# 1LED_pulldown.net
KiCad netlist of a schematic drawn in EAGLE
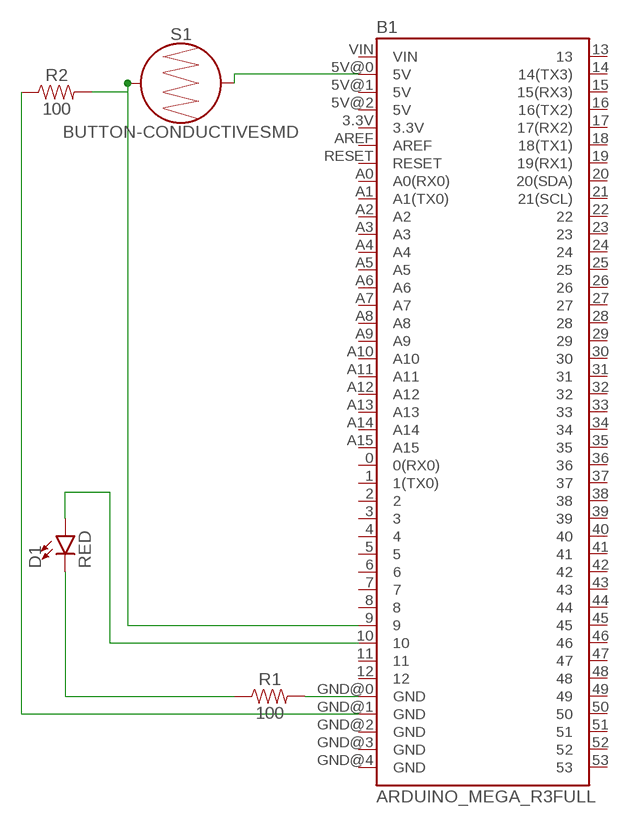
[diagram p0: schematic, sheet 1]

(export (version "E")
  (design (tool "Eeschema 10.0.6"))
  (components
    (comp (ref "B1")
      (value "ARDUINO_MEGA_R3FULL")
      (footprint "eagle-import:ARDUINO_MEGA")
      (libsource (lib "eagle-import") (part "ARDUINO_MEGA_R3FULL"))
    )
    (comp (ref "D1")
      (value "RED")
      (footprint "eagle-import:LED-0603")
      (libsource (lib "eagle-import") (part "LED-RED0603"))
    )
    (comp (ref "R1")
      (value "100")
      (footprint "eagle-import:0603")
      (libsource (lib "eagle-import") (part "100OHM-0603-1/4W-5%"))
    )
    (comp (ref "R2")
      (value "100")
      (footprint "eagle-import:0603")
      (libsource (lib "eagle-import") (part "100OHM-0603-1/4W-5%"))
    )
    (comp (ref "S1")
      (value "BUTTON-CONDUCTIVESMD")
      (footprint "eagle-import:BUTTON-CONDUCTIVE")
      (libsource (lib "eagle-import") (part "BUTTON-CONDUCTIVESMD"))
    )
  )
  (nets
    (net (code "1") (name "Net-(B1-5V-Pad5V@0)") (class "Default")
      (node (ref "B1") (pin "5V@0") (pinfunction "5V_5V@0") (pintype "bidirectional"))
      (node (ref "S1") (pin "2") (pinfunction "2_2") (pintype "passive"))
    )
    (net (code "2") (name "Net-(B1-GND-PadGND@0)") (class "Default")
      (node (ref "B1") (pin "GND@0") (pinfunction "GND_GND@0") (pintype "bidirectional"))
      (node (ref "R1") (pin "2") (pinfunction "2_2") (pintype "passive"))
    )
    (net (code "3") (name "Net-(B1-GND-PadGND@1)") (class "Default")
      (node (ref "B1") (pin "GND@1") (pinfunction "GND_GND@1") (pintype "bidirectional"))
      (node (ref "R2") (pin "1") (pinfunction "1_1") (pintype "passive"))
    )
    (net (code "4") (name "Net-(B1-Pad9)") (class "Default")
      (node (ref "B1") (pin "9") (pinfunction "9_9") (pintype "bidirectional"))
      (node (ref "R2") (pin "2") (pinfunction "2_2") (pintype "passive"))
      (node (ref "S1") (pin "1") (pinfunction "1_1") (pintype "passive"))
    )
    (net (code "5") (name "Net-(B1-Pad10)") (class "Default")
      (node (ref "B1") (pin "10") (pinfunction "10_10") (pintype "bidirectional"))
      (node (ref "D1") (pin "A") (pinfunction "A_A") (pintype "passive"))
    )
    (net (code "6") (name "Net-(D1-PadC)") (class "Default")
      (node (ref "D1") (pin "C") (pinfunction "C_C") (pintype "passive"))
      (node (ref "R1") (pin "1") (pinfunction "1_1") (pintype "passive"))
    )
    (net (code "7") (name "unconnected-(B1-0(RX0)-Pad0)") (class "Default")
      (node (ref "B1") (pin "0") (pinfunction "0(RX0)_0") (pintype "bidirectional"))
    )
    (net (code "8") (name "unconnected-(B1-1(TX0)-Pad1)") (class "Default")
      (node (ref "B1") (pin "1") (pinfunction "1(TX0)_1") (pintype "bidirectional"))
    )
    (net (code "9") (name "unconnected-(B1-5V-Pad5V@1)") (class "Default")
      (node (ref "B1") (pin "5V@1") (pinfunction "5V_5V@1") (pintype "bidirectional"))
    )
    (net (code "10") (name "unconnected-(B1-5V-Pad5V@2)") (class "Default")
      (node (ref "B1") (pin "5V@2") (pinfunction "5V_5V@2") (pintype "bidirectional"))
    )
    (net (code "11") (name "unconnected-(B1-14(TX3)-Pad14)") (class "Default")
      (node (ref "B1") (pin "14") (pinfunction "14(TX3)_14") (pintype "bidirectional"))
    )
    (net (code "12") (name "unconnected-(B1-15(RX3)-Pad15)") (class "Default")
      (node (ref "B1") (pin "15") (pinfunction "15(RX3)_15") (pintype "bidirectional"))
    )
    (net (code "13") (name "unconnected-(B1-16(TX2)-Pad16)") (class "Default")
      (node (ref "B1") (pin "16") (pinfunction "16(TX2)_16") (pintype "bidirectional"))
    )
    (net (code "14") (name "unconnected-(B1-17(RX2)-Pad17)") (class "Default")
      (node (ref "B1") (pin "17") (pinfunction "17(RX2)_17") (pintype "bidirectional"))
    )
    (net (code "15") (name "unconnected-(B1-18(TX1)-Pad18)") (class "Default")
      (node (ref "B1") (pin "18") (pinfunction "18(TX1)_18") (pintype "bidirectional"))
    )
    (net (code "16") (name "unconnected-(B1-19(RX1)-Pad19)") (class "Default")
      (node (ref "B1") (pin "19") (pinfunction "19(RX1)_19") (pintype "bidirectional"))
    )
    (net (code "17") (name "unconnected-(B1-20(SDA)-Pad20)") (class "Default")
      (node (ref "B1") (pin "20") (pinfunction "20(SDA)_20") (pintype "bidirectional"))
    )
    (net (code "18") (name "unconnected-(B1-21(SCL)-Pad21)") (class "Default")
      (node (ref "B1") (pin "21") (pinfunction "21(SCL)_21") (pintype "bidirectional"))
    )
    (net (code "19") (name "unconnected-(B1-A0(RX0)-PadA0)") (class "Default")
      (node (ref "B1") (pin "A0") (pinfunction "A0(RX0)_A0") (pintype "bidirectional"))
    )
    (net (code "20") (name "unconnected-(B1-A1(TX0)-PadA1)") (class "Default")
      (node (ref "B1") (pin "A1") (pinfunction "A1(TX0)_A1") (pintype "bidirectional"))
    )
    (net (code "21") (name "unconnected-(B1-GND-PadGND@2)") (class "Default")
      (node (ref "B1") (pin "GND@2") (pinfunction "GND_GND@2") (pintype "bidirectional"))
    )
    (net (code "22") (name "unconnected-(B1-GND-PadGND@3)") (class "Default")
      (node (ref "B1") (pin "GND@3") (pinfunction "GND_GND@3") (pintype "bidirectional"))
    )
    (net (code "23") (name "unconnected-(B1-GND-PadGND@4)") (class "Default")
      (node (ref "B1") (pin "GND@4") (pinfunction "GND_GND@4") (pintype "bidirectional"))
    )
    (net (code "24") (name "unconnected-(B1-Pad2)") (class "Default")
      (node (ref "B1") (pin "2") (pinfunction "2_2") (pintype "bidirectional"))
    )
    (net (code "25") (name "unconnected-(B1-Pad3)") (class "Default")
      (node (ref "B1") (pin "3") (pinfunction "3_3") (pintype "bidirectional"))
    )
    (net (code "26") (name "unconnected-(B1-Pad3.3V)") (class "Default")
      (node (ref "B1") (pin "3.3V") (pinfunction "3.3V_3.3V") (pintype "bidirectional"))
    )
    (net (code "27") (name "unconnected-(B1-Pad4)") (class "Default")
      (node (ref "B1") (pin "4") (pinfunction "4_4") (pintype "bidirectional"))
    )
    (net (code "28") (name "unconnected-(B1-Pad5)") (class "Default")
      (node (ref "B1") (pin "5") (pinfunction "5_5") (pintype "bidirectional"))
    )
    (net (code "29") (name "unconnected-(B1-Pad6)") (class "Default")
      (node (ref "B1") (pin "6") (pinfunction "6_6") (pintype "bidirectional"))
    )
    (net (code "30") (name "unconnected-(B1-Pad7)") (class "Default")
      (node (ref "B1") (pin "7") (pinfunction "7_7") (pintype "bidirectional"))
    )
    (net (code "31") (name "unconnected-(B1-Pad8)") (class "Default")
      (node (ref "B1") (pin "8") (pinfunction "8_8") (pintype "bidirectional"))
    )
    (net (code "32") (name "unconnected-(B1-Pad11)") (class "Default")
      (node (ref "B1") (pin "11") (pinfunction "11_11") (pintype "bidirectional"))
    )
    (net (code "33") (name "unconnected-(B1-Pad12)") (class "Default")
      (node (ref "B1") (pin "12") (pinfunction "12_12") (pintype "bidirectional"))
    )
    (net (code "34") (name "unconnected-(B1-Pad13)") (class "Default")
      (node (ref "B1") (pin "13") (pinfunction "13_13") (pintype "bidirectional"))
    )
    (net (code "35") (name "unconnected-(B1-Pad22)") (class "Default")
      (node (ref "B1") (pin "22") (pinfunction "22_22") (pintype "bidirectional"))
    )
    (net (code "36") (name "unconnected-(B1-Pad23)") (class "Default")
      (node (ref "B1") (pin "23") (pinfunction "23_23") (pintype "bidirectional"))
    )
    (net (code "37") (name "unconnected-(B1-Pad24)") (class "Default")
      (node (ref "B1") (pin "24") (pinfunction "24_24") (pintype "bidirectional"))
    )
    (net (code "38") (name "unconnected-(B1-Pad25)") (class "Default")
      (node (ref "B1") (pin "25") (pinfunction "25_25") (pintype "bidirectional"))
    )
    (net (code "39") (name "unconnected-(B1-Pad26)") (class "Default")
      (node (ref "B1") (pin "26") (pinfunction "26_26") (pintype "bidirectional"))
    )
    (net (code "40") (name "unconnected-(B1-Pad27)") (class "Default")
      (node (ref "B1") (pin "27") (pinfunction "27_27") (pintype "bidirectional"))
    )
    (net (code "41") (name "unconnected-(B1-Pad28)") (class "Default")
      (node (ref "B1") (pin "28") (pinfunction "28_28") (pintype "bidirectional"))
    )
    (net (code "42") (name "unconnected-(B1-Pad29)") (class "Default")
      (node (ref "B1") (pin "29") (pinfunction "29_29") (pintype "bidirectional"))
    )
    (net (code "43") (name "unconnected-(B1-Pad30)") (class "Default")
      (node (ref "B1") (pin "30") (pinfunction "30_30") (pintype "bidirectional"))
    )
    (net (code "44") (name "unconnected-(B1-Pad31)") (class "Default")
      (node (ref "B1") (pin "31") (pinfunction "31_31") (pintype "bidirectional"))
    )
    (net (code "45") (name "unconnected-(B1-Pad32)") (class "Default")
      (node (ref "B1") (pin "32") (pinfunction "32_32") (pintype "bidirectional"))
    )
    (net (code "46") (name "unconnected-(B1-Pad33)") (class "Default")
      (node (ref "B1") (pin "33") (pinfunction "33_33") (pintype "bidirectional"))
    )
    (net (code "47") (name "unconnected-(B1-Pad34)") (class "Default")
      (node (ref "B1") (pin "34") (pinfunction "34_34") (pintype "bidirectional"))
    )
    (net (code "48") (name "unconnected-(B1-Pad35)") (class "Default")
      (node (ref "B1") (pin "35") (pinfunction "35_35") (pintype "bidirectional"))
    )
    (net (code "49") (name "unconnected-(B1-Pad36)") (class "Default")
      (node (ref "B1") (pin "36") (pinfunction "36_36") (pintype "bidirectional"))
    )
    (net (code "50") (name "unconnected-(B1-Pad37)") (class "Default")
      (node (ref "B1") (pin "37") (pinfunction "37_37") (pintype "bidirectional"))
    )
    (net (code "51") (name "unconnected-(B1-Pad38)") (class "Default")
      (node (ref "B1") (pin "38") (pinfunction "38_38") (pintype "bidirectional"))
    )
    (net (code "52") (name "unconnected-(B1-Pad39)") (class "Default")
      (node (ref "B1") (pin "39") (pinfunction "39_39") (pintype "bidirectional"))
    )
    (net (code "53") (name "unconnected-(B1-Pad40)") (class "Default")
      (node (ref "B1") (pin "40") (pinfunction "40_40") (pintype "bidirectional"))
    )
    (net (code "54") (name "unconnected-(B1-Pad41)") (class "Default")
      (node (ref "B1") (pin "41") (pinfunction "41_41") (pintype "bidirectional"))
    )
    (net (code "55") (name "unconnected-(B1-Pad42)") (class "Default")
      (node (ref "B1") (pin "42") (pinfunction "42_42") (pintype "bidirectional"))
    )
    (net (code "56") (name "unconnected-(B1-Pad43)") (class "Default")
      (node (ref "B1") (pin "43") (pinfunction "43_43") (pintype "bidirectional"))
    )
    (net (code "57") (name "unconnected-(B1-Pad44)") (class "Default")
      (node (ref "B1") (pin "44") (pinfunction "44_44") (pintype "bidirectional"))
    )
    (net (code "58") (name "unconnected-(B1-Pad45)") (class "Default")
      (node (ref "B1") (pin "45") (pinfunction "45_45") (pintype "bidirectional"))
    )
    (net (code "59") (name "unconnected-(B1-Pad46)") (class "Default")
      (node (ref "B1") (pin "46") (pinfunction "46_46") (pintype "bidirectional"))
    )
    (net (code "60") (name "unconnected-(B1-Pad47)") (class "Default")
      (node (ref "B1") (pin "47") (pinfunction "47_47") (pintype "bidirectional"))
    )
    (net (code "61") (name "unconnected-(B1-Pad48)") (class "Default")
      (node (ref "B1") (pin "48") (pinfunction "48_48") (pintype "bidirectional"))
    )
    (net (code "62") (name "unconnected-(B1-Pad49)") (class "Default")
      (node (ref "B1") (pin "49") (pinfunction "49_49") (pintype "bidirectional"))
    )
    (net (code "63") (name "unconnected-(B1-Pad50)") (class "Default")
      (node (ref "B1") (pin "50") (pinfunction "50_50") (pintype "bidirectional"))
    )
    (net (code "64") (name "unconnected-(B1-Pad51)") (class "Default")
      (node (ref "B1") (pin "51") (pinfunction "51_51") (pintype "bidirectional"))
    )
    (net (code "65") (name "unconnected-(B1-Pad52)") (class "Default")
      (node (ref "B1") (pin "52") (pinfunction "52_52") (pintype "bidirectional"))
    )
    (net (code "66") (name "unconnected-(B1-Pad53)") (class "Default")
      (node (ref "B1") (pin "53") (pinfunction "53_53") (pintype "bidirectional"))
    )
    (net (code "67") (name "unconnected-(B1-PadA2)") (class "Default")
      (node (ref "B1") (pin "A2") (pinfunction "A2_A2") (pintype "bidirectional"))
    )
    (net (code "68") (name "unconnected-(B1-PadA3)") (class "Default")
      (node (ref "B1") (pin "A3") (pinfunction "A3_A3") (pintype "bidirectional"))
    )
    (net (code "69") (name "unconnected-(B1-PadA4)") (class "Default")
      (node (ref "B1") (pin "A4") (pinfunction "A4_A4") (pintype "bidirectional"))
    )
    (net (code "70") (name "unconnected-(B1-PadA5)") (class "Default")
      (node (ref "B1") (pin "A5") (pinfunction "A5_A5") (pintype "bidirectional"))
    )
    (net (code "71") (name "unconnected-(B1-PadA6)") (class "Default")
      (node (ref "B1") (pin "A6") (pinfunction "A6_A6") (pintype "bidirectional"))
    )
    (net (code "72") (name "unconnected-(B1-PadA7)") (class "Default")
      (node (ref "B1") (pin "A7") (pinfunction "A7_A7") (pintype "bidirectional"))
    )
    (net (code "73") (name "unconnected-(B1-PadA8)") (class "Default")
      (node (ref "B1") (pin "A8") (pinfunction "A8_A8") (pintype "bidirectional"))
    )
    (net (code "74") (name "unconnected-(B1-PadA9)") (class "Default")
      (node (ref "B1") (pin "A9") (pinfunction "A9_A9") (pintype "bidirectional"))
    )
    (net (code "75") (name "unconnected-(B1-PadA10)") (class "Default")
      (node (ref "B1") (pin "A10") (pinfunction "A10_A10") (pintype "bidirectional"))
    )
    (net (code "76") (name "unconnected-(B1-PadA11)") (class "Default")
      (node (ref "B1") (pin "A11") (pinfunction "A11_A11") (pintype "bidirectional"))
    )
    (net (code "77") (name "unconnected-(B1-PadA12)") (class "Default")
      (node (ref "B1") (pin "A12") (pinfunction "A12_A12") (pintype "bidirectional"))
    )
    (net (code "78") (name "unconnected-(B1-PadA13)") (class "Default")
      (node (ref "B1") (pin "A13") (pinfunction "A13_A13") (pintype "bidirectional"))
    )
    (net (code "79") (name "unconnected-(B1-PadA14)") (class "Default")
      (node (ref "B1") (pin "A14") (pinfunction "A14_A14") (pintype "bidirectional"))
    )
    (net (code "80") (name "unconnected-(B1-PadA15)") (class "Default")
      (node (ref "B1") (pin "A15") (pinfunction "A15_A15") (pintype "bidirectional"))
    )
    (net (code "81") (name "unconnected-(B1-PadAREF)") (class "Default")
      (node (ref "B1") (pin "AREF") (pinfunction "AREF_AREF") (pintype "bidirectional"))
    )
    (net (code "82") (name "unconnected-(B1-PadRESET)") (class "Default")
      (node (ref "B1") (pin "RESET") (pinfunction "RESET_RESET") (pintype "bidirectional"))
    )
    (net (code "83") (name "unconnected-(B1-PadVIN)") (class "Default")
      (node (ref "B1") (pin "VIN") (pinfunction "VIN_VIN") (pintype "bidirectional"))
    )
  )
)
